# IV_sensing.net
KiCad netlist of a schematic drawn in Altium Designer
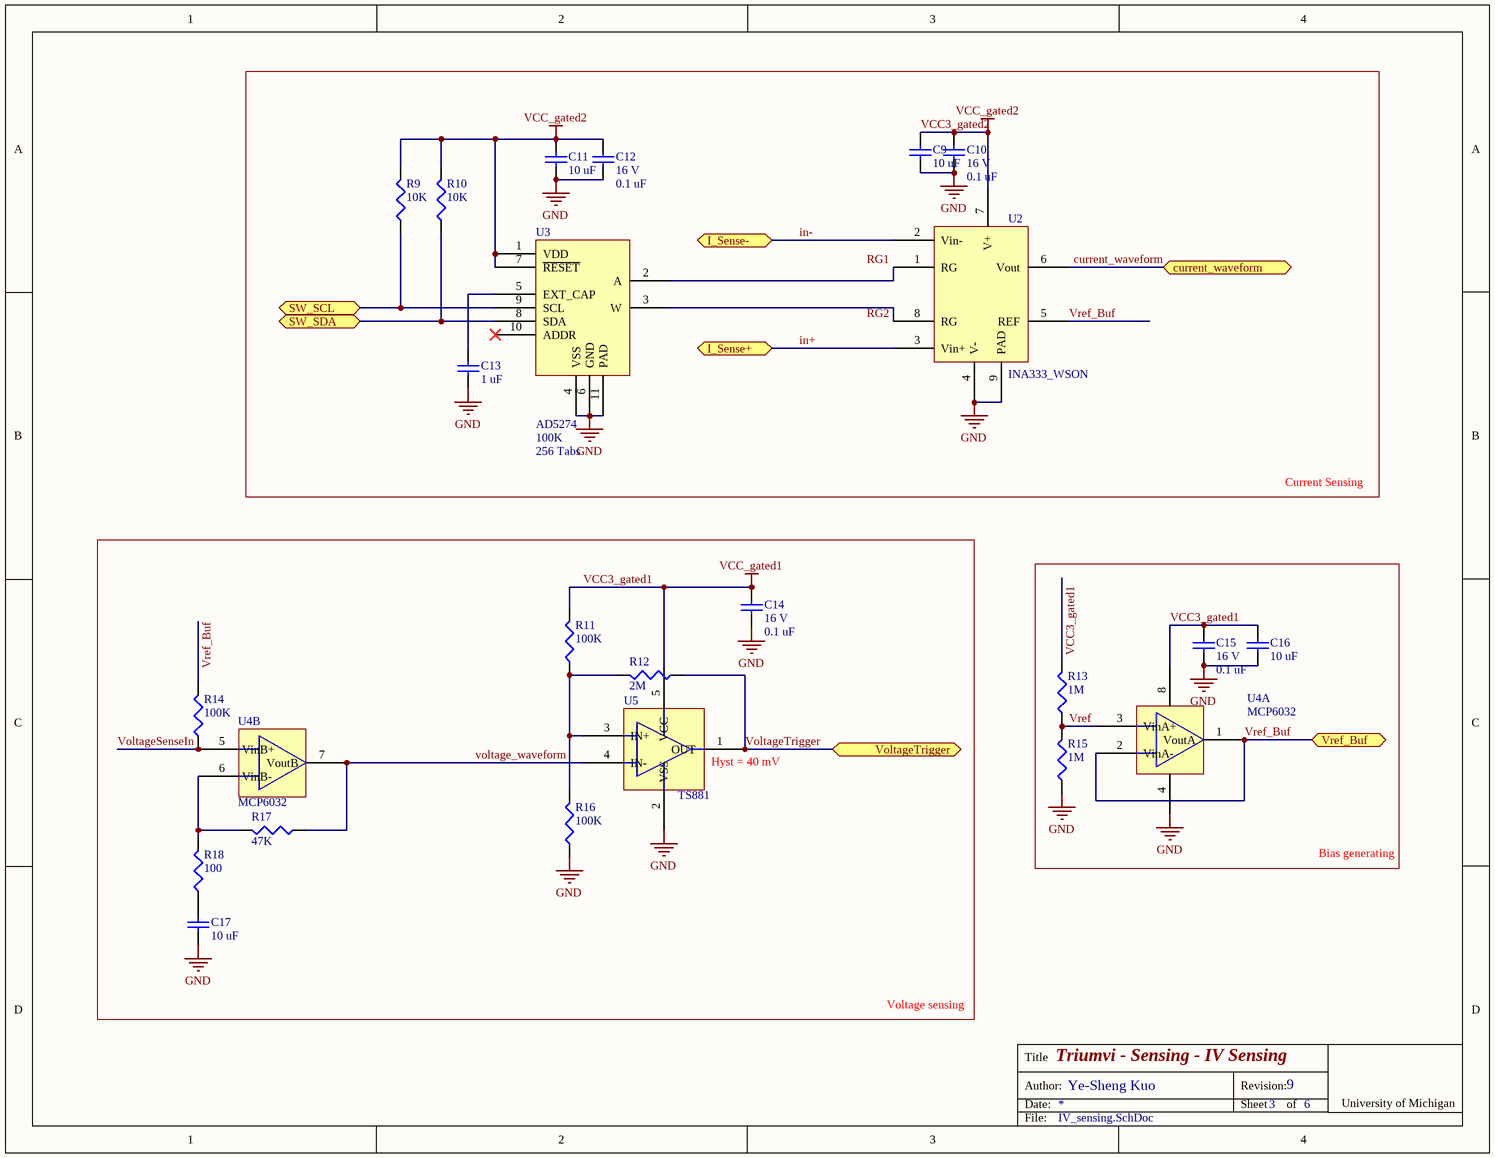
[diagram p0: IV_sensing.SchDoc]

(export (version "E")
  (design (tool "Eeschema 10.0.6"))
  (components
    (comp (ref "C9")
      (value "10 uF")
      (footprint "0603")
      (description "Ceramic capacitor, 10 uF, 0603 package")
      (fields (field (name "TOLERANCE") "20%") (field (name "Comment") "Ceramic capacitor"))
      (libsource (lib "rlc") (part "C_10u_6.3V_0603_ceramic"))
    )
    (comp (ref "C10")
      (value "0.1 uF")
      (footprint "0402")
      (description "Ceramic capacitor, 0.1u, 16 V, 0402 package")
      (fields
        (field (name "VOLTAGE RATED") "16 V")
        (field (name "TOLERANCE") "10%")
        (field (name "Comment") "Ceramic capacitor")
      )
      (libsource (lib "rlc") (part "C_0.1u_16V_0402_ceramic"))
    )
    (comp (ref "C11")
      (value "10 uF")
      (footprint "0603")
      (description "Ceramic capacitor, 10 uF, 0603 package")
      (fields (field (name "TOLERANCE") "20%") (field (name "Comment") "Ceramic capacitor"))
      (libsource (lib "rlc") (part "C_10u_6.3V_0603_ceramic"))
    )
    (comp (ref "C12")
      (value "0.1 uF")
      (footprint "0402")
      (description "Ceramic capacitor, 0.1u, 16 V, 0402 package")
      (fields
        (field (name "VOLTAGE RATED") "16 V")
        (field (name "TOLERANCE") "10%")
        (field (name "Comment") "Ceramic capacitor")
      )
      (libsource (lib "rlc") (part "C_0.1u_16V_0402_ceramic"))
    )
    (comp (ref "C13")
      (value "1 uF")
      (footprint "0402")
      (description "Ceramic capacitor, 1 uF, 16V, 0402 package")
      (fields (field (name "TOLERANCE") "10%") (field (name "Comment") "Ceramic capacitor"))
      (libsource (lib "rlc") (part "C_1u_16V_0402_ceramic"))
    )
    (comp (ref "C14")
      (value "0.1 uF")
      (footprint "0402")
      (description "Ceramic capacitor, 0.1u, 16 V, 0402 package")
      (fields
        (field (name "VOLTAGE RATED") "16 V")
        (field (name "TOLERANCE") "10%")
        (field (name "Comment") "Ceramic capacitor")
      )
      (libsource (lib "rlc") (part "C_0.1u_16V_0402_ceramic"))
    )
    (comp (ref "C15")
      (value "0.1 uF")
      (footprint "0402")
      (description "Ceramic capacitor, 0.1u, 16 V, 0402 package")
      (fields
        (field (name "VOLTAGE RATED") "16 V")
        (field (name "TOLERANCE") "10%")
        (field (name "Comment") "Ceramic capacitor")
      )
      (libsource (lib "rlc") (part "C_0.1u_16V_0402_ceramic"))
    )
    (comp (ref "C16")
      (value "10 uF")
      (footprint "0603")
      (description "Ceramic capacitor, 10 uF, 0603 package")
      (fields (field (name "TOLERANCE") "20%") (field (name "Comment") "Ceramic capacitor"))
      (libsource (lib "rlc") (part "C_10u_6.3V_0603_ceramic"))
    )
    (comp (ref "C17")
      (value "10 uF")
      (footprint "0603")
      (description "Ceramic capacitor, 10 uF, 0603 package")
      (fields (field (name "TOLERANCE") "20%") (field (name "Comment") "Ceramic capacitor"))
      (libsource (lib "rlc") (part "C_10u_6.3V_0603_ceramic"))
    )
    (comp (ref "R9")
      (value "10K")
      (footprint "0402")
      (description "Chip resistor, 10K, 0402 package")
      (fields (field (name "TOLERANCE") "1%") (field (name "POWER") "1/16 W"))
      (libsource (lib "rlc") (part "R_10K_0402"))
    )
    (comp (ref "R10")
      (value "10K")
      (footprint "0402")
      (description "Chip resistor, 10K, 0402 package")
      (fields (field (name "TOLERANCE") "1%") (field (name "POWER") "1/16 W"))
      (libsource (lib "rlc") (part "R_10K_0402"))
    )
    (comp (ref "R11")
      (value "100K")
      (footprint "0402")
      (description "Chip resistor, 100K, 0402 package")
      (fields (field (name "TOLERANCE") "1%") (field (name "POWER") "1/16 W"))
      (libsource (lib "rlc") (part "R_100K_0402"))
    )
    (comp (ref "R12")
      (value "2M")
      (footprint "0402")
      (description "Chip resistor, 2M, 0402 package")
      (fields (field (name "TOLERANCE") "1%") (field (name "POWER") "1/16 W"))
      (libsource (lib "rlc") (part "R_2M_0402"))
    )
    (comp (ref "R13")
      (value "1M")
      (footprint "0402")
      (description "Chip resistor, 1M, 0402 package")
      (fields (field (name "TOLERANCE") "1%") (field (name "POWER") "1/16 W"))
      (libsource (lib "rlc") (part "R_1M_0402"))
    )
    (comp (ref "R14")
      (value "100K")
      (footprint "0402")
      (description "Chip resistor, 100K, 0402 package")
      (fields (field (name "TOLERANCE") "1%") (field (name "POWER") "1/16 W"))
      (libsource (lib "rlc") (part "R_100K_0402"))
    )
    (comp (ref "R15")
      (value "1M")
      (footprint "0402")
      (description "Chip resistor, 1M, 0402 package")
      (fields (field (name "TOLERANCE") "1%") (field (name "POWER") "1/16 W"))
      (libsource (lib "rlc") (part "R_1M_0402"))
    )
    (comp (ref "R16")
      (value "100K")
      (footprint "0402")
      (description "Chip resistor, 100K, 0402 package")
      (fields (field (name "TOLERANCE") "1%") (field (name "POWER") "1/16 W"))
      (libsource (lib "rlc") (part "R_100K_0402"))
    )
    (comp (ref "R17")
      (value "47K")
      (footprint "0402")
      (description "Chip resistor, 47K, 0402 package")
      (fields (field (name "TOLERANCE") "1%") (field (name "POWER") "1/16 W"))
      (libsource (lib "rlc") (part "R_47K_0402"))
    )
    (comp (ref "R18")
      (value "100")
      (footprint "0402")
      (description "Chip resistor, 100, 0402 package")
      (fields (field (name "TOLERANCE") "1%") (field (name "POWER") "1/16 W"))
      (libsource (lib "rlc") (part "R_100_0402"))
    )
    (comp (ref "U2")
      (value "INA333_WSON")
      (footprint "WSON-8")
      (description "Micro-Power (50µA), Zerø-Drift, Rail-to-Rail Out  Instrumentation Amplifier")
      (libsource (lib "amplifier") (part "INA333_WSON"))
    )
    (comp (ref "U3")
      (value "AD5274")
      (footprint "LFCSP_WD")
      (description "1024-/256-Position, 1% Resistor Tolerance Error, I2C Interface and 50-TP Memory Digital Rheostat")
      (fields (field (name "ALTIUM_VALUE") "100K") (field (name "ALTIUM_UNNAMED_1") "256 Tabs"))
      (libsource (lib "digital_potentiometer") (part "AD5274"))
    )
    (comp (ref "U4")
      (value "MCP6032")
      (footprint "MSOP-8")
      (description "0.9 µA, High Precision Op Amps")
      (libsource (lib "amplifier") (part "MCP6032"))
    )
    (comp (ref "U5")
      (value "TS881")
      (footprint "SC70-5")
      (description "Rail-to-rail 0.9 V nanopower comparator")
      (libsource (lib "comparators") (part "TS881"))
    )
  )
  (nets
    (net (code "3") (name "/SW_SCL") (class "Default")
      (node (ref "R9") (pin "2") (pintype "passive"))
      (node (ref "U3") (pin "9") (pinfunction "SCL_9") (pintype "passive"))
    )
    (net (code "4") (name "/SW_SDA") (class "Default")
      (node (ref "R10") (pin "2") (pintype "passive"))
      (node (ref "U3") (pin "8") (pinfunction "SDA_8") (pintype "passive"))
    )
    (net (code "5") (name "/VoltageSenseIn") (class "Default")
      (node (ref "R14") (pin "2") (pintype "passive"))
      (node (ref "U4") (pin "5") (pinfunction "VinB+_5") (pintype "passive"))
    )
    (net (code "6") (name "/VoltageTrigger") (class "Default")
      (node (ref "R12") (pin "2") (pintype "passive"))
      (node (ref "U5") (pin "1") (pinfunction "OUT_1") (pintype "passive"))
    )
    (net (code "7") (name "/Vref") (class "Default")
      (node (ref "R13") (pin "2") (pintype "passive"))
      (node (ref "R15") (pin "1") (pintype "passive"))
      (node (ref "U4") (pin "3") (pinfunction "VinA+_3") (pintype "passive"))
    )
    (net (code "8") (name "/Vref_Buf") (class "Default")
      (node (ref "R14") (pin "1") (pintype "passive"))
      (node (ref "U2") (pin "5") (pinfunction "REF_5") (pintype "passive"))
      (node (ref "U4") (pin "1") (pinfunction "VoutA_1") (pintype "passive"))
      (node (ref "U4") (pin "2") (pinfunction "VinA-_2") (pintype "passive"))
    )
    (net (code "9") (name "/current_waveform") (class "Default")
      (node (ref "U2") (pin "6") (pinfunction "Vout_6") (pintype "passive"))
    )
    (net (code "10") (name "/in+") (class "Default")
      (node (ref "U2") (pin "3") (pinfunction "Vin+_3") (pintype "passive"))
    )
    (net (code "11") (name "/in-") (class "Default")
      (node (ref "U2") (pin "2") (pinfunction "Vin-_2") (pintype "passive"))
    )
    (net (code "12") (name "/voltage_waveform") (class "Default")
      (node (ref "R17") (pin "2") (pintype "passive"))
      (node (ref "U4") (pin "7") (pinfunction "VoutB_7") (pintype "passive"))
      (node (ref "U5") (pin "4") (pinfunction "IN-_4") (pintype "passive"))
    )
    (net (code "13") (name "GND") (class "Default")
      (node (ref "C10") (pin "2") (pintype "passive"))
      (node (ref "C11") (pin "2") (pintype "passive"))
      (node (ref "C12") (pin "2") (pintype "passive"))
      (node (ref "C13") (pin "2") (pintype "passive"))
      (node (ref "C14") (pin "2") (pintype "passive"))
      (node (ref "C15") (pin "2") (pintype "passive"))
      (node (ref "C16") (pin "2") (pintype "passive"))
      (node (ref "C17") (pin "2") (pintype "passive"))
      (node (ref "C9") (pin "2") (pintype "passive"))
      (node (ref "R15") (pin "2") (pintype "passive"))
      (node (ref "R16") (pin "2") (pintype "passive"))
      (node (ref "U2") (pin "4") (pinfunction "V-_4") (pintype "passive"))
      (node (ref "U2") (pin "9") (pinfunction "PAD_9") (pintype "passive"))
      (node (ref "U3") (pin "11") (pinfunction "PAD_11") (pintype "passive"))
      (node (ref "U3") (pin "4") (pinfunction "VSS_4") (pintype "passive"))
      (node (ref "U3") (pin "6") (pinfunction "GND_6") (pintype "passive"))
      (node (ref "U4") (pin "4") (pinfunction "VSS_4") (pintype "passive"))
      (node (ref "U5") (pin "2") (pinfunction "VSS_2") (pintype "passive"))
    )
    (net (code "14") (name "Net-(C17-Pad1)") (class "Default")
      (node (ref "C17") (pin "1") (pintype "passive"))
      (node (ref "R18") (pin "2") (pintype "passive"))
    )
    (net (code "15") (name "Net-(U3-A)") (class "Default")
      (node (ref "U2") (pin "1") (pinfunction "RG_1") (pintype "passive"))
      (node (ref "U3") (pin "2") (pinfunction "A_2") (pintype "passive"))
    )
    (net (code "16") (name "Net-(U3-EXT_CAP)") (class "Default")
      (node (ref "C13") (pin "1") (pintype "passive"))
      (node (ref "U3") (pin "5") (pinfunction "EXT_CAP_5") (pintype "passive"))
    )
    (net (code "17") (name "Net-(U3-W)") (class "Default")
      (node (ref "U2") (pin "8") (pinfunction "RG_8") (pintype "passive"))
      (node (ref "U3") (pin "3") (pinfunction "W_3") (pintype "passive"))
    )
    (net (code "18") (name "Net-(U4B-VinB-)") (class "Default")
      (node (ref "R17") (pin "1") (pintype "passive"))
      (node (ref "R18") (pin "1") (pintype "passive"))
      (node (ref "U4") (pin "6") (pinfunction "VinB-_6") (pintype "passive"))
    )
    (net (code "19") (name "Net-(U5-IN+)") (class "Default")
      (node (ref "R11") (pin "2") (pintype "passive"))
      (node (ref "R12") (pin "1") (pintype "passive"))
      (node (ref "R16") (pin "1") (pintype "passive"))
      (node (ref "U5") (pin "3") (pinfunction "IN+_3") (pintype "passive"))
    )
    (net (code "20") (name "VCC_gated1") (class "Default")
      (node (ref "C14") (pin "1") (pintype "passive"))
      (node (ref "C15") (pin "1") (pintype "passive"))
      (node (ref "C16") (pin "1") (pintype "passive"))
      (node (ref "R11") (pin "1") (pintype "passive"))
      (node (ref "R13") (pin "1") (pintype "passive"))
      (node (ref "U4") (pin "8") (pinfunction "VDD_8") (pintype "passive"))
      (node (ref "U5") (pin "5") (pinfunction "VCC_5") (pintype "passive"))
    )
    (net (code "21") (name "VCC_gated2") (class "Default")
      (node (ref "C10") (pin "1") (pintype "passive"))
      (node (ref "C11") (pin "1") (pintype "passive"))
      (node (ref "C12") (pin "1") (pintype "passive"))
      (node (ref "C9") (pin "1") (pintype "passive"))
      (node (ref "R10") (pin "1") (pintype "passive"))
      (node (ref "R9") (pin "1") (pintype "passive"))
      (node (ref "U2") (pin "7") (pinfunction "V+_7") (pintype "passive"))
      (node (ref "U3") (pin "1") (pinfunction "VDD_1") (pintype "passive"))
      (node (ref "U3") (pin "7") (pinfunction "~{RESET}_7") (pintype "passive"))
    )
    (net (code "22") (name "unconnected-(U3-ADDR-Pad10)") (class "Default")
      (node (ref "U3") (pin "10") (pinfunction "ADDR_10") (pintype "passive+no_connect"))
    )
  )
)
